# USB_2.net
KiCad netlist of a schematic drawn in Altium Designer
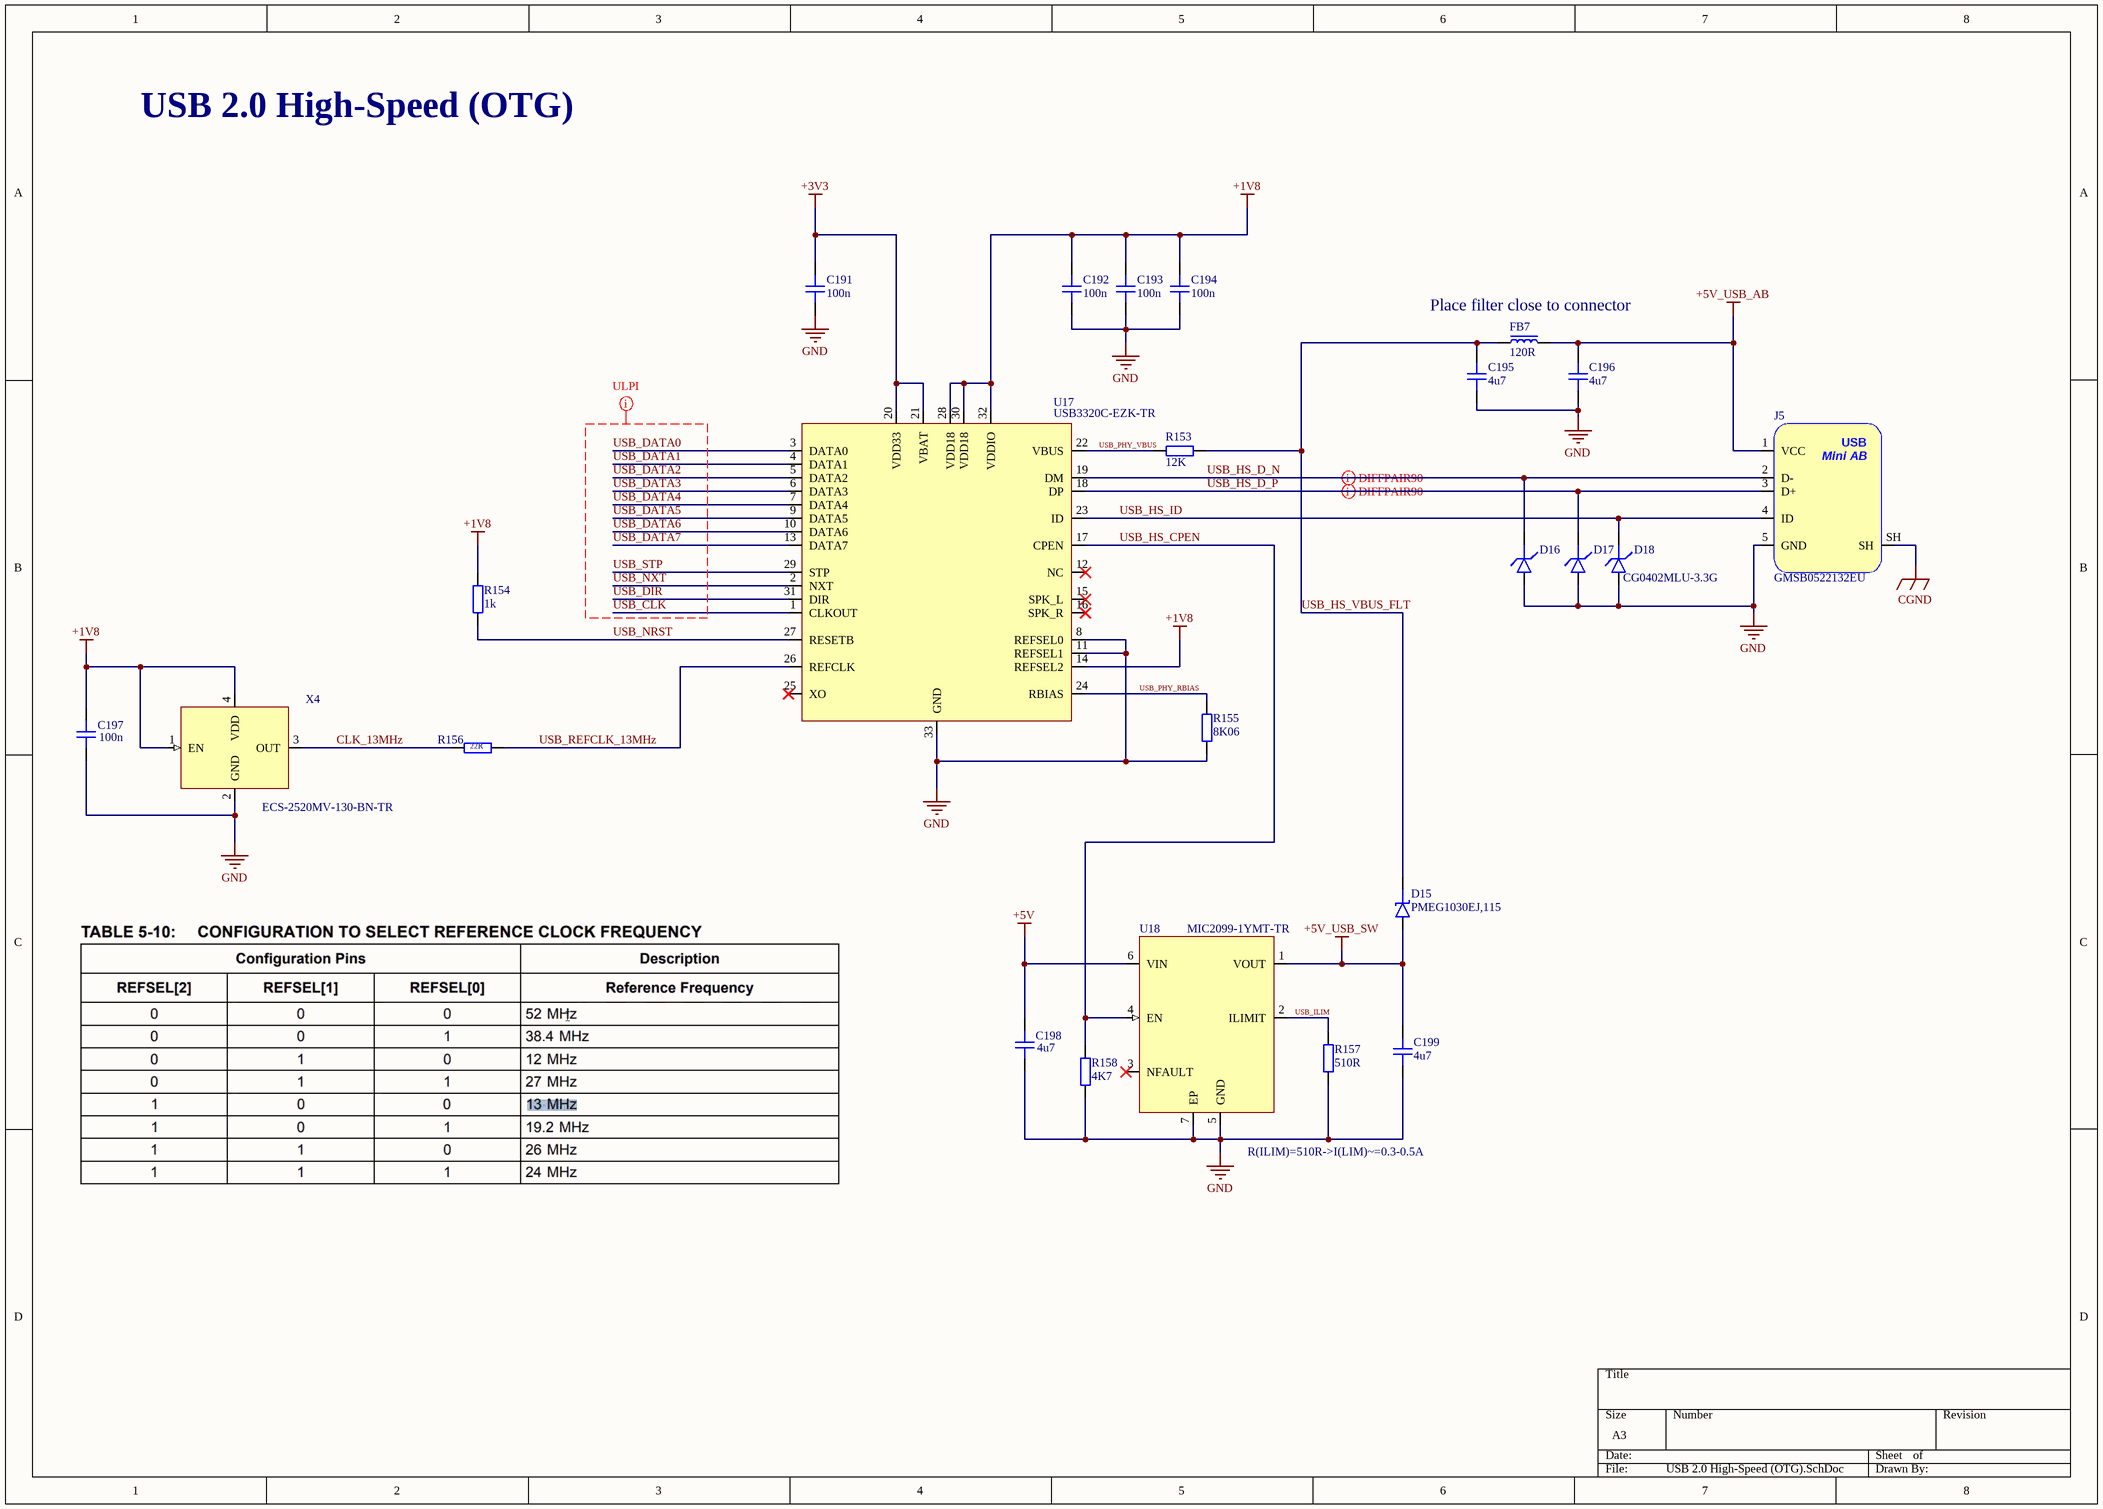
[diagram p0: USB 2.0 High-Speed (OTG).SchDoc]

(export (version "E")
  (design (tool "Eeschema 10.0.6"))
  (components
    (comp (ref "C191")
      (value "100n")
      (footprint "CAP_0402")
      (description "Capacitor SMD 0402")
      (libsource (lib "Schematic-Lib-PhilsLab") (part "CAP_0402"))
    )
    (comp (ref "C192")
      (value "100n")
      (footprint "CAP_0402")
      (description "Capacitor SMD 0402")
      (libsource (lib "Schematic-Lib-PhilsLab") (part "CAP_0402"))
    )
    (comp (ref "C193")
      (value "100n")
      (footprint "CAP_0402")
      (description "Capacitor SMD 0402")
      (libsource (lib "Schematic-Lib-PhilsLab") (part "CAP_0402"))
    )
    (comp (ref "C194")
      (value "100n")
      (footprint "CAP_0402")
      (description "Capacitor SMD 0402")
      (libsource (lib "Schematic-Lib-PhilsLab") (part "CAP_0402"))
    )
    (comp (ref "C195")
      (value "4u7")
      (footprint "CAP_0402")
      (description "Capacitor SMD 0402")
      (libsource (lib "Schematic-Lib-PhilsLab") (part "CAP_0402"))
    )
    (comp (ref "C196")
      (value "4u7")
      (footprint "CAP_0402")
      (description "Capacitor SMD 0402")
      (libsource (lib "Schematic-Lib-PhilsLab") (part "CAP_0402"))
    )
    (comp (ref "C197")
      (value "100n")
      (footprint "CAP_0402")
      (description "Capacitor SMD 0402")
      (fields (field (name "Comment") "C0402"))
      (libsource (lib "Schematic-Lib-PhilsLab") (part "CAP_0402"))
    )
    (comp (ref "C198")
      (value "4u7")
      (footprint "CAP_0402")
      (description "Capacitor SMD 0402")
      (fields (field (name "Comment") "C0402"))
      (libsource (lib "Schematic-Lib-PhilsLab") (part "CAP_0402"))
    )
    (comp (ref "C199")
      (value "4u7")
      (footprint "CAP_0402")
      (description "Capacitor SMD 0402")
      (fields (field (name "Comment") "C0402"))
      (libsource (lib "Schematic-Lib-PhilsLab") (part "CAP_0402"))
    )
    (comp (ref "D15")
      (value "PMEG1030EJ,115")
      (footprint "SOD-323")
      (description "Diode Schottky SMD SOD-323")
      (libsource (lib "Schematic-Lib-PhilsLab") (part "D_SCHOTTKY_SOD_323"))
    )
    (comp (ref "D16")
      (value "D_TVS_0402")
      (footprint "D_0402")
      (description "Diode TVS / ESD 0402")
      (libsource (lib "Schematic-Lib-PhilsLab") (part "D_TVS_0402"))
    )
    (comp (ref "D17")
      (value "D_TVS_0402")
      (footprint "D_0402")
      (description "Diode TVS / ESD 0402")
      (libsource (lib "Schematic-Lib-PhilsLab") (part "D_TVS_0402"))
    )
    (comp (ref "D18")
      (value "D_TVS_0402")
      (footprint "D_0402")
      (description "Diode TVS / ESD 0402")
      (fields (field (name "DESIGNATOR") "CG0402MLU-3.3G"))
      (libsource (lib "Schematic-Lib-PhilsLab") (part "D_TVS_0402"))
    )
    (comp (ref "FB7")
      (value "120R")
      (footprint "FB_0402")
      (description "Ferrite Bead SMD 0402")
      (libsource (lib "Schematic-Lib-PhilsLab") (part "FB_0402"))
    )
    (comp (ref "J5")
      (value "GMSB0522132EU")
      (footprint "GMSB0522132EU")
      (description "USB 2.0 Mini AB Receptacle Right Angle Through-Hole")
      (fields (field (name "MANUFACTURER") "Amphenol"))
      (libsource (lib "Schematic-Lib-PhilsLab") (part "GMSB0522132EU"))
    )
    (comp (ref "R153")
      (value "12K")
      (footprint "RES_0402")
      (description "Resistor SMD 0402")
      (fields (field (name "Comment") "R0402"))
      (libsource (lib "Schematic-Lib-PhilsLab") (part "RES_0402"))
    )
    (comp (ref "R154")
      (value "1k")
      (footprint "RES_0402")
      (description "Resistor SMD 0402")
      (fields (field (name "Comment") "R0402"))
      (libsource (lib "Schematic-Lib-PhilsLab") (part "RES_0402"))
    )
    (comp (ref "R155")
      (value "8K06")
      (footprint "RES_0402")
      (description "Resistor SMD 0402")
      (fields (field (name "Comment") "R0402"))
      (libsource (lib "Schematic-Lib-PhilsLab") (part "RES_0402"))
    )
    (comp (ref "R156")
      (value "22R")
      (footprint "RES_0402")
      (description "Resistor SMD 0402")
      (fields (field (name "Comment") "R0402"))
      (libsource (lib "Schematic-Lib-PhilsLab") (part "RES_0402"))
    )
    (comp (ref "R157")
      (value "510R")
      (footprint "RES_0402")
      (description "Resistor SMD 0402")
      (fields (field (name "Comment") "R0402"))
      (libsource (lib "Schematic-Lib-PhilsLab") (part "RES_0402"))
    )
    (comp (ref "R158")
      (value "4K7")
      (footprint "RES_0402")
      (description "Resistor SMD 0402")
      (fields (field (name "Comment") "R0402"))
      (libsource (lib "Schematic-Lib-PhilsLab") (part "RES_0402"))
    )
    (comp (ref "U17")
      (value "USB3320C-EZK-TR")
      (footprint "QFN-32-5x5x0.85mm")
      (description "Hi-Speed USB 2.0 ULPI Transceiver")
      (fields (field (name "MANUFACTURER") "Microchip"))
      (libsource (lib "Schematic-Lib-PhilsLab") (part "USB3320C-EZK-TR"))
    )
    (comp (ref "U18")
      (value "MIC2099-1YMT-TR")
      (footprint "TMLF-6-1_6X1_6")
      (description "Power Distribution Switch Resistor programmable current limit\r\n– 0.1A to 1.1A 2.5V-5.5V")
      (fields (field (name "MANUFACTURER") "Microchip"))
      (libsource (lib "Schematic-Lib-PhilsLab") (part "MIC2099-1YMT-TR"))
    )
    (comp (ref "X4")
      (value "ECS-2520MV-130-BN-TR")
      (footprint "XTAL_2520")
      (fields (field (name "MANUFACTURER") "ECS"))
      (libsource (lib "Schematic-Lib-PhilsLab") (part "ECS-2520MV-130-BN-TR"))
    )
  )
  (nets
    (net (code "1") (name "+1V8") (class "Default")
      (node (ref "C192") (pin "2") (pinfunction "2_2") (pintype "passive"))
      (node (ref "C193") (pin "2") (pinfunction "2_2") (pintype "passive"))
      (node (ref "C194") (pin "2") (pinfunction "2_2") (pintype "passive"))
      (node (ref "C197") (pin "2") (pinfunction "2_2") (pintype "passive"))
      (node (ref "R154") (pin "1") (pinfunction "1_1") (pintype "passive"))
      (node (ref "U17") (pin "14") (pinfunction "REFSEL2_14") (pintype "passive"))
      (node (ref "U17") (pin "28") (pinfunction "VDD18_28") (pintype "passive"))
      (node (ref "U17") (pin "30") (pinfunction "VDD18_30") (pintype "passive"))
      (node (ref "U17") (pin "32") (pinfunction "VDDIO_32") (pintype "passive"))
      (node (ref "X4") (pin "1") (pinfunction "EN_1") (pintype "input"))
      (node (ref "X4") (pin "4") (pinfunction "VDD_4") (pintype "power_in"))
    )
    (net (code "2") (name "+3V3") (class "Default")
      (node (ref "C191") (pin "2") (pinfunction "2_2") (pintype "passive"))
      (node (ref "U17") (pin "20") (pinfunction "VDD33_20") (pintype "passive"))
      (node (ref "U17") (pin "21") (pinfunction "VBAT_21") (pintype "passive"))
    )
    (net (code "3") (name "+5V") (class "Default")
      (node (ref "C198") (pin "2") (pinfunction "2_2") (pintype "passive"))
      (node (ref "U18") (pin "6") (pinfunction "VIN_6") (pintype "power_in"))
    )
    (net (code "4") (name "+5V_USB_AB") (class "Default")
      (node (ref "C196") (pin "2") (pinfunction "2_2") (pintype "passive"))
      (node (ref "FB7") (pin "2") (pinfunction "2_2") (pintype "passive"))
      (node (ref "J5") (pin "1") (pinfunction "VCC_1") (pintype "power_in"))
    )
    (net (code "5") (name "+5V_USB_SW") (class "Default")
      (node (ref "C199") (pin "2") (pinfunction "2_2") (pintype "passive"))
      (node (ref "D15") (pin "A") (pinfunction "A_A") (pintype "passive"))
      (node (ref "U18") (pin "1") (pinfunction "VOUT_1") (pintype "power_in"))
    )
    (net (code "6") (name "/CLK_13MHz") (class "Default")
      (node (ref "R156") (pin "2") (pinfunction "2_2") (pintype "passive"))
      (node (ref "X4") (pin "3") (pinfunction "OUT_3") (pintype "passive"))
    )
    (net (code "7") (name "/USB_CLK") (class "Default")
      (node (ref "U17") (pin "1") (pinfunction "CLKOUT_1") (pintype "passive"))
    )
    (net (code "8") (name "/USB_DATA0") (class "Default")
      (node (ref "U17") (pin "3") (pinfunction "DATA0_3") (pintype "passive"))
    )
    (net (code "9") (name "/USB_DATA1") (class "Default")
      (node (ref "U17") (pin "4") (pinfunction "DATA1_4") (pintype "passive"))
    )
    (net (code "10") (name "/USB_DATA2") (class "Default")
      (node (ref "U17") (pin "5") (pinfunction "DATA2_5") (pintype "passive"))
    )
    (net (code "11") (name "/USB_DATA3") (class "Default")
      (node (ref "U17") (pin "6") (pinfunction "DATA3_6") (pintype "passive"))
    )
    (net (code "12") (name "/USB_DATA4") (class "Default")
      (node (ref "U17") (pin "7") (pinfunction "DATA4_7") (pintype "passive"))
    )
    (net (code "13") (name "/USB_DATA5") (class "Default")
      (node (ref "U17") (pin "9") (pinfunction "DATA5_9") (pintype "passive"))
    )
    (net (code "14") (name "/USB_DATA6") (class "Default")
      (node (ref "U17") (pin "10") (pinfunction "DATA6_10") (pintype "passive"))
    )
    (net (code "15") (name "/USB_DATA7") (class "Default")
      (node (ref "U17") (pin "13") (pinfunction "DATA7_13") (pintype "passive"))
    )
    (net (code "16") (name "/USB_DIR") (class "Default")
      (node (ref "U17") (pin "31") (pinfunction "DIR_31") (pintype "passive"))
    )
    (net (code "17") (name "/USB_HS_CPEN") (class "Default")
      (node (ref "R158") (pin "1") (pinfunction "1_1") (pintype "passive"))
      (node (ref "U17") (pin "17") (pinfunction "CPEN_17") (pintype "passive"))
      (node (ref "U18") (pin "4") (pinfunction "EN_4") (pintype "input"))
    )
    (net (code "18") (name "/USB_HS_D_N") (class "Default")
      (node (ref "D16") (pin "K") (pinfunction "K_K") (pintype "passive"))
      (node (ref "J5") (pin "2") (pinfunction "D-_2") (pintype "bidirectional"))
      (node (ref "U17") (pin "19") (pinfunction "DM_19") (pintype "passive"))
    )
    (net (code "19") (name "/USB_HS_D_P") (class "Default")
      (node (ref "D17") (pin "K") (pinfunction "K_K") (pintype "passive"))
      (node (ref "J5") (pin "3") (pinfunction "D+_3") (pintype "bidirectional"))
      (node (ref "U17") (pin "18") (pinfunction "DP_18") (pintype "passive"))
    )
    (net (code "20") (name "/USB_HS_ID") (class "Default")
      (node (ref "D18") (pin "K") (pinfunction "K_K") (pintype "passive"))
      (node (ref "J5") (pin "4") (pinfunction "ID_4") (pintype "passive"))
      (node (ref "U17") (pin "23") (pinfunction "ID_23") (pintype "passive"))
    )
    (net (code "21") (name "/USB_HS_VBUS_FLT") (class "Default")
      (node (ref "C195") (pin "2") (pinfunction "2_2") (pintype "passive"))
      (node (ref "D15") (pin "K") (pinfunction "K_K") (pintype "passive"))
      (node (ref "FB7") (pin "1") (pinfunction "1_1") (pintype "passive"))
      (node (ref "R153") (pin "2") (pinfunction "2_2") (pintype "passive"))
    )
    (net (code "22") (name "/USB_ILIM") (class "Default")
      (node (ref "R157") (pin "1") (pinfunction "1_1") (pintype "passive"))
      (node (ref "U18") (pin "2") (pinfunction "ILIMIT_2") (pintype "passive"))
    )
    (net (code "23") (name "/USB_NRST") (class "Default")
      (node (ref "R154") (pin "2") (pinfunction "2_2") (pintype "passive"))
      (node (ref "U17") (pin "27") (pinfunction "RESETB_27") (pintype "passive"))
    )
    (net (code "24") (name "/USB_NXT") (class "Default")
      (node (ref "U17") (pin "2") (pinfunction "NXT_2") (pintype "passive"))
    )
    (net (code "25") (name "/USB_PHY_RBIAS") (class "Default")
      (node (ref "R155") (pin "1") (pinfunction "1_1") (pintype "passive"))
      (node (ref "U17") (pin "24") (pinfunction "RBIAS_24") (pintype "passive"))
    )
    (net (code "26") (name "/USB_PHY_VBUS") (class "Default")
      (node (ref "R153") (pin "1") (pinfunction "1_1") (pintype "passive"))
      (node (ref "U17") (pin "22") (pinfunction "VBUS_22") (pintype "passive"))
    )
    (net (code "27") (name "/USB_REFCLK_13MHz") (class "Default")
      (node (ref "R156") (pin "1") (pinfunction "1_1") (pintype "passive"))
      (node (ref "U17") (pin "26") (pinfunction "REFCLK_26") (pintype "passive"))
    )
    (net (code "28") (name "/USB_STP") (class "Default")
      (node (ref "U17") (pin "29") (pinfunction "STP_29") (pintype "passive"))
    )
    (net (code "29") (name "CGND") (class "Default")
      (node (ref "J5") (pin "SH") (pinfunction "SH_SH") (pintype "power_in"))
    )
    (net (code "30") (name "GND") (class "Default")
      (node (ref "C191") (pin "1") (pinfunction "1_1") (pintype "passive"))
      (node (ref "C192") (pin "1") (pinfunction "1_1") (pintype "passive"))
      (node (ref "C193") (pin "1") (pinfunction "1_1") (pintype "passive"))
      (node (ref "C194") (pin "1") (pinfunction "1_1") (pintype "passive"))
      (node (ref "C195") (pin "1") (pinfunction "1_1") (pintype "passive"))
      (node (ref "C196") (pin "1") (pinfunction "1_1") (pintype "passive"))
      (node (ref "C197") (pin "1") (pinfunction "1_1") (pintype "passive"))
      (node (ref "C198") (pin "1") (pinfunction "1_1") (pintype "passive"))
      (node (ref "C199") (pin "1") (pinfunction "1_1") (pintype "passive"))
      (node (ref "D16") (pin "A") (pinfunction "A_A") (pintype "passive"))
      (node (ref "D17") (pin "A") (pinfunction "A_A") (pintype "passive"))
      (node (ref "D18") (pin "A") (pinfunction "A_A") (pintype "passive"))
      (node (ref "J5") (pin "5") (pinfunction "GND_5") (pintype "power_in"))
      (node (ref "R155") (pin "2") (pinfunction "2_2") (pintype "passive"))
      (node (ref "R157") (pin "2") (pinfunction "2_2") (pintype "passive"))
      (node (ref "R158") (pin "2") (pinfunction "2_2") (pintype "passive"))
      (node (ref "U17") (pin "11") (pinfunction "REFSEL1_11") (pintype "passive"))
      (node (ref "U17") (pin "33") (pinfunction "GND_33") (pintype "passive"))
      (node (ref "U17") (pin "8") (pinfunction "REFSEL0_8") (pintype "passive"))
      (node (ref "U18") (pin "5") (pinfunction "GND_5") (pintype "power_in"))
      (node (ref "U18") (pin "7") (pinfunction "EP_7") (pintype "power_in"))
      (node (ref "X4") (pin "2") (pinfunction "GND_2") (pintype "power_in"))
    )
    (net (code "31") (name "unconnected-(U17-NC-Pad12)") (class "Default")
      (node (ref "U17") (pin "12") (pinfunction "NC_12") (pintype "passive+no_connect"))
    )
    (net (code "32") (name "unconnected-(U17-SPK_L-Pad15)") (class "Default")
      (node (ref "U17") (pin "15") (pinfunction "SPK_L_15") (pintype "passive+no_connect"))
    )
    (net (code "33") (name "unconnected-(U17-SPK_R-Pad16)") (class "Default")
      (node (ref "U17") (pin "16") (pinfunction "SPK_R_16") (pintype "passive+no_connect"))
    )
    (net (code "34") (name "unconnected-(U17-XO-Pad25)") (class "Default")
      (node (ref "U17") (pin "25") (pinfunction "XO_25") (pintype "passive+no_connect"))
    )
    (net (code "35") (name "unconnected-(U18-NFAULT-Pad3)") (class "Default")
      (node (ref "U18") (pin "3") (pinfunction "NFAULT_3") (pintype "open_collector+no_connect"))
    )
  )
)
